# PWR_MGMT.net
KiCad netlist of a schematic drawn in Altium Designer
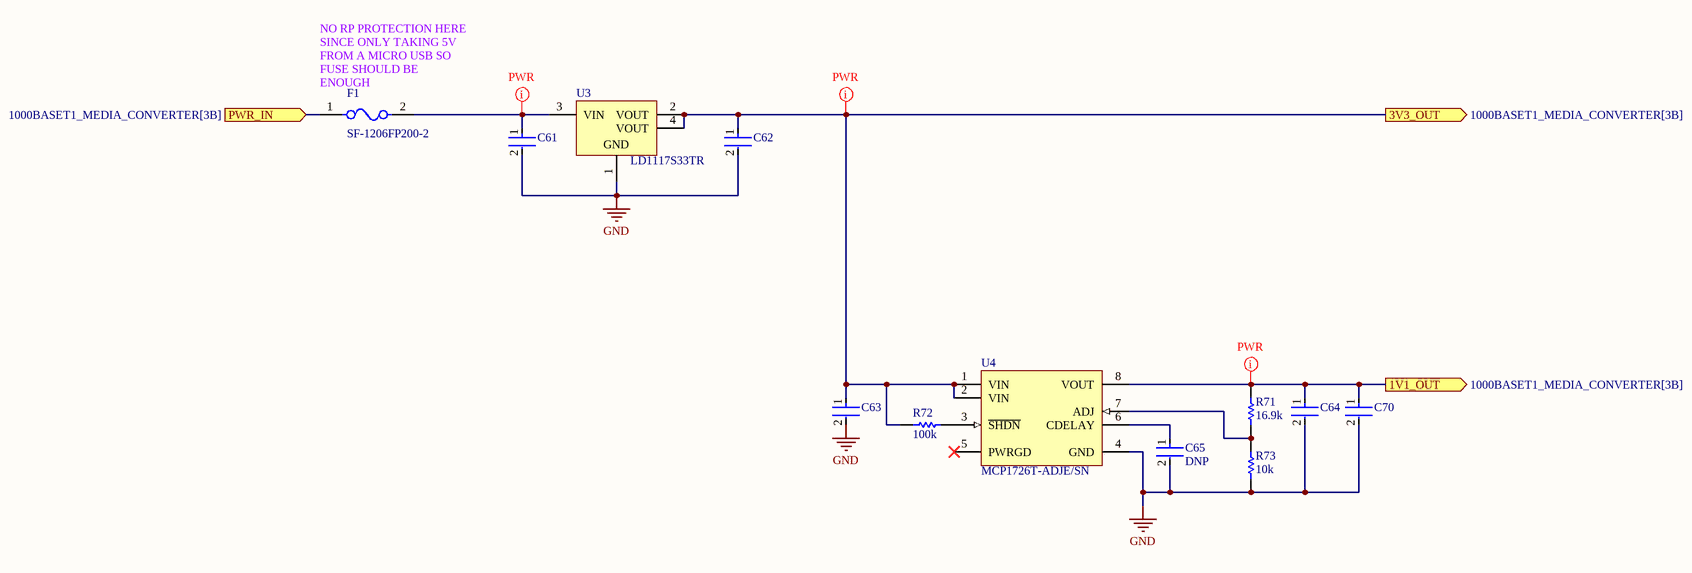
[diagram p0: PWR_MGMT.SchDoc]

(export (version "E")
  (design (tool "Eeschema 10.0.6"))
  (components
    (comp (ref "C61")
      (value "C0805C475J4RACAUTO")
      (footprint "FP-C0805C475J4RACAUTO-MFG")
      (description "C0805C475J4RACAUTO Cap Ceramic 4.7uF 16V X7R 5% Pad SMD 0805 125C Automotive T/R")
      (fields (field (name "TOLERANCE") "5%"))
      (libsource (lib "Altium Content Vault") (part "b4654b650e69147ec39a6b967a45e02"))
    )
    (comp (ref "C62")
      (value "GRM21BR61E226ME44L")
      (footprint "FP-GRM21B-0_2-e0_2_0_7-IPC_B")
      (description "Chip Multilayer Ceramic Capacitors for General Purpose, 0805, 22uF, X5R, 15%, 20%, 25V")
      (fields (field (name "TOLERANCE") "20%") (field (name "VOLTAGE") "25V"))
      (libsource (lib "Altium Content Vault") (part "b4654b650e69147ec39a6b967a45e02"))
    )
    (comp (ref "C63")
      (value "C0805C475J4RACAUTO")
      (footprint "FP-C0805C475J4RACAUTO-MFG")
      (description "C0805C475J4RACAUTO Cap Ceramic 4.7uF 16V X7R 5% Pad SMD 0805 125C Automotive T/R")
      (fields (field (name "TOLERANCE") "5%"))
      (libsource (lib "Altium Content Vault") (part "b4654b650e69147ec39a6b967a45e02"))
    )
    (comp (ref "C64")
      (value "GRM21BR61E226ME44L")
      (footprint "FP-GRM21B-0_2-e0_2_0_7-IPC_B")
      (description "Chip Multilayer Ceramic Capacitors for General Purpose, 0805, 22uF, X5R, 15%, 20%, 25V")
      (fields (field (name "TOLERANCE") "20%") (field (name "VOLTAGE") "25V"))
      (libsource (lib "Altium Content Vault") (part "b4654b650e69147ec39a6b967a45e02"))
    )
    (comp (ref "C65")
      (value "DNP")
      (footprint "FP-0402-L_1_0_0_05-W_0_5-IPC_A")
      (description "LARGE PADS, 0402 CAP, CHANGE COMMENT TO MATCH REAL P/N")
      (libsource (lib "Space Concordia") (part "b4654b650e69147ec39a6b967a45e02"))
    )
    (comp (ref "C70")
      (value "C0805C475J4RACAUTO")
      (footprint "FP-C0805C475J4RACAUTO-MFG")
      (description "C0805C475J4RACAUTO Cap Ceramic 4.7uF 16V X7R 5% Pad SMD 0805 125C Automotive T/R")
      (fields (field (name "TOLERANCE") "5%"))
      (libsource (lib "Altium Content Vault") (part "b4654b650e69147ec39a6b967a45e02"))
    )
    (comp (ref "F1")
      (value "SF-1206FP200-2")
      (footprint "FP-SF-1206FP-MFG")
      (description "FUSE BOARD MOUNT 2A 63VDC 1206")
      (libsource (lib "Altium Content Vault") (part "5bcf9b9f640e542cf0359d10258e979"))
    )
    (comp (ref "R71")
      (value "16.9k")
      (footprint "R0603B")
      (description "Resistor")
      (libsource (lib "Space Concordia") (part "Resistor"))
    )
    (comp (ref "R72")
      (value "100k")
      (footprint "R0603B")
      (description "Resistor")
      (libsource (lib "Space Concordia") (part "Resistor"))
    )
    (comp (ref "R73")
      (value "10k")
      (footprint "R0603B")
      (description "Resistor")
      (libsource (lib "Space Concordia") (part "Resistor"))
    )
    (comp (ref "U3")
      (value "LD1117S33TR")
      (footprint "SOT-223_L")
      (description "Fixed Low Drop Positive Voltage Regulator, 3.3V, 4-Pin SOT-223, Tape and Reel")
      (libsource (lib "Altium Content Vault") (part "PM-REG-LD1117-SOT4"))
    )
    (comp (ref "U4")
      (value "MCP1726T-ADJE/SN")
      (footprint "SOIC-SN8_L")
      (libsource (lib "Altium Content Vault") (part "PM-LINEREG-MCP1726-IL8A"))
    )
  )
  (nets
    (net (code "1") (name "/1V1_OUT") (class "Default")
      (node (ref "C64") (pin "1") (pinfunction "1_1") (pintype "passive"))
      (node (ref "C70") (pin "1") (pinfunction "1_1") (pintype "passive"))
      (node (ref "R71") (pin "2") (pinfunction "2_2") (pintype "passive"))
      (node (ref "U4") (pin "8") (pinfunction "VOUT_8") (pintype "power_in"))
    )
    (net (code "2") (name "/3V3_OUT") (class "Default")
      (node (ref "C62") (pin "1") (pinfunction "1_1") (pintype "passive"))
      (node (ref "C63") (pin "1") (pinfunction "1_1") (pintype "passive"))
      (node (ref "R72") (pin "1") (pinfunction "1_1") (pintype "passive"))
      (node (ref "U3") (pin "2") (pinfunction "VOUT_2") (pintype "power_in"))
      (node (ref "U3") (pin "4") (pinfunction "VOUT_4") (pintype "power_in"))
      (node (ref "U4") (pin "1") (pinfunction "VIN_1") (pintype "power_in"))
      (node (ref "U4") (pin "2") (pinfunction "VIN_2") (pintype "power_in"))
    )
    (net (code "3") (name "/PWR_IN") (class "Default")
      (node (ref "F1") (pin "1") (pinfunction "1_1") (pintype "passive"))
    )
    (net (code "4") (name "GND") (class "Default")
      (node (ref "C61") (pin "2") (pinfunction "2_2") (pintype "passive"))
      (node (ref "C62") (pin "2") (pinfunction "2_2") (pintype "passive"))
      (node (ref "C63") (pin "2") (pinfunction "2_2") (pintype "passive"))
      (node (ref "C64") (pin "2") (pinfunction "2_2") (pintype "passive"))
      (node (ref "C65") (pin "2") (pinfunction "2_2") (pintype "passive"))
      (node (ref "C70") (pin "2") (pinfunction "2_2") (pintype "passive"))
      (node (ref "R73") (pin "1") (pinfunction "1_1") (pintype "passive"))
      (node (ref "U3") (pin "1") (pinfunction "GND_1") (pintype "power_in"))
      (node (ref "U4") (pin "4") (pinfunction "GND_4") (pintype "power_in"))
    )
    (net (code "5") (name "Net-(U3-VIN)") (class "Default")
      (node (ref "C61") (pin "1") (pinfunction "1_1") (pintype "passive"))
      (node (ref "F1") (pin "2") (pinfunction "2_2") (pintype "passive"))
      (node (ref "U3") (pin "3") (pinfunction "VIN_3") (pintype "power_in"))
    )
    (net (code "6") (name "Net-(U4-ADJ)") (class "Default")
      (node (ref "R71") (pin "1") (pinfunction "1_1") (pintype "passive"))
      (node (ref "R73") (pin "2") (pinfunction "2_2") (pintype "passive"))
      (node (ref "U4") (pin "7") (pinfunction "ADJ_7") (pintype "input"))
    )
    (net (code "7") (name "Net-(U4-CDELAY)") (class "Default")
      (node (ref "C65") (pin "1") (pinfunction "1_1") (pintype "passive"))
      (node (ref "U4") (pin "6") (pinfunction "CDELAY_6") (pintype "passive"))
    )
    (net (code "8") (name "Net-(U4-~{SHDN})") (class "Default")
      (node (ref "R72") (pin "2") (pinfunction "2_2") (pintype "passive"))
      (node (ref "U4") (pin "3") (pinfunction "~{SHDN}_3") (pintype "input"))
    )
    (net (code "9") (name "unconnected-(U4-PWRGD-Pad5)") (class "Default")
      (node (ref "U4") (pin "5") (pinfunction "PWRGD_5") (pintype "power_in+no_connect"))
    )
  )
)
